# Nexie.net
KiCad netlist of a schematic drawn in Altium Designer
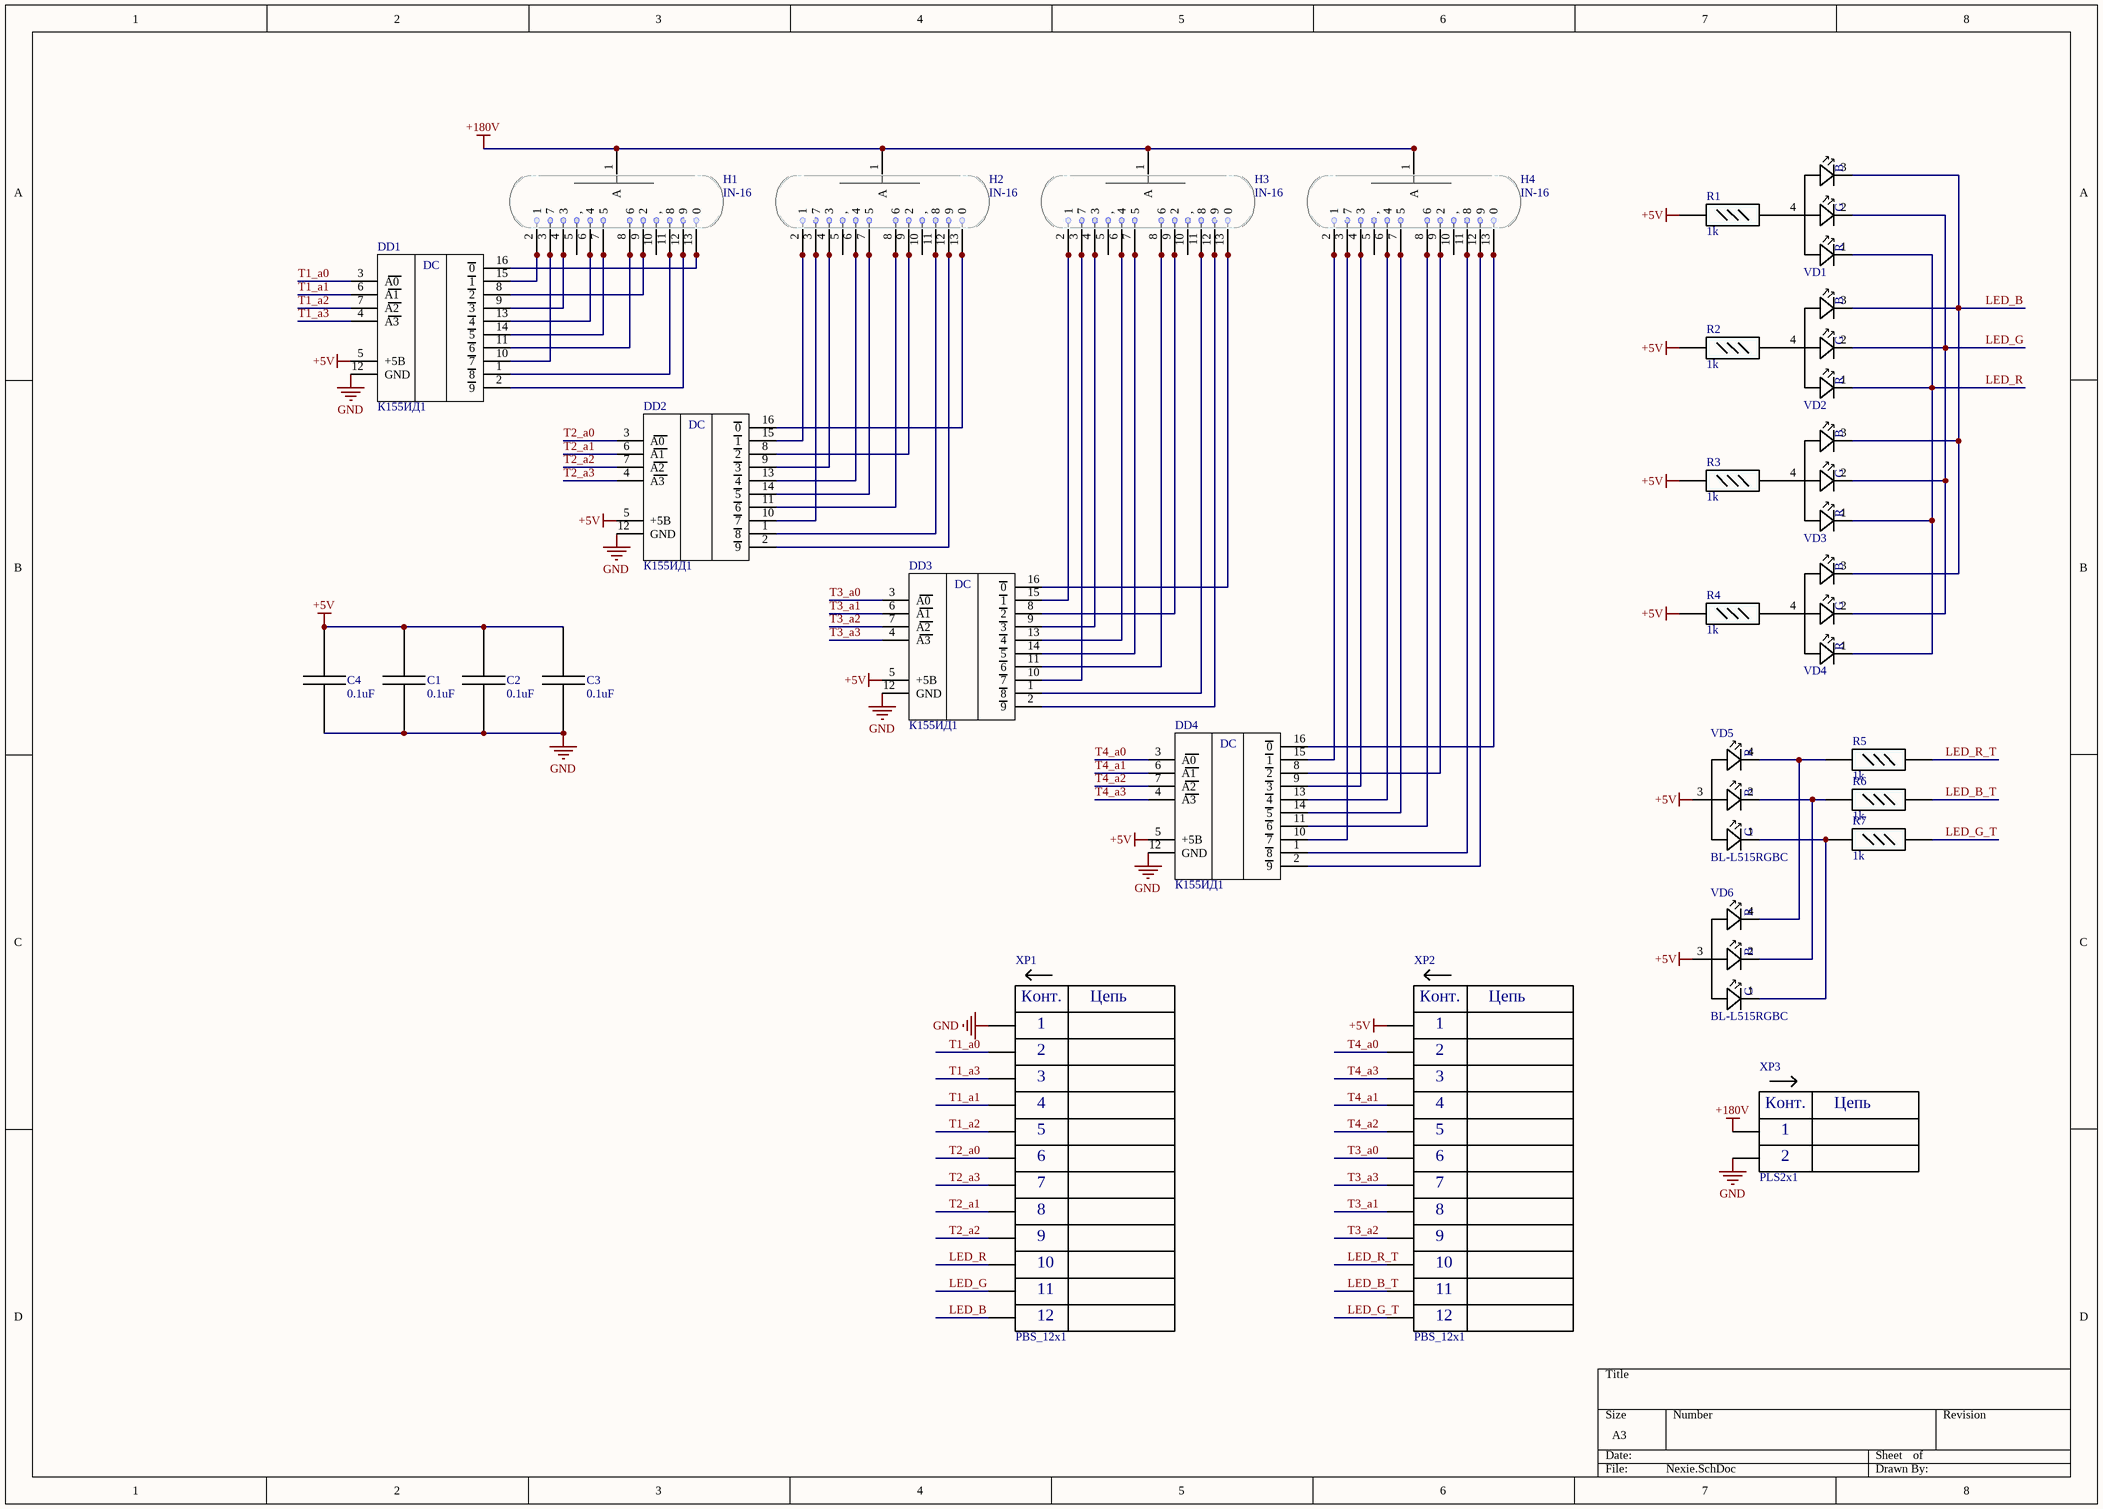
[diagram p0: Nexie.SchDoc]

(export (version "E")
  (design (tool "Eeschema 10.0.6"))
  (components
    (comp (ref "C1")
      (value "0.1uF")
      (footprint "CAP_1206")
      (fields (field (name "Comment") "Cap_0"))
      (libsource (lib "Capacitor") (part "Cap_0"))
    )
    (comp (ref "C2")
      (value "0.1uF")
      (footprint "CAP_1206")
      (fields (field (name "Comment") "Cap_0"))
      (libsource (lib "Capacitor") (part "Cap_0"))
    )
    (comp (ref "C3")
      (value "0.1uF")
      (footprint "CAP_1206")
      (fields (field (name "Comment") "Cap_0"))
      (libsource (lib "Capacitor") (part "Cap_0"))
    )
    (comp (ref "C4")
      (value "0.1uF")
      (footprint "CAP_1206")
      (fields (field (name "Comment") "Cap_0"))
      (libsource (lib "Capacitor") (part "Cap_0"))
    )
    (comp (ref "DD1") (value "К155ИД1") (footprint "К155ИД1") (libsource (lib "K155") (part "К155ИД1")))
    (comp (ref "DD2") (value "К155ИД1") (footprint "К155ИД1") (libsource (lib "K155") (part "К155ИД1")))
    (comp (ref "DD3") (value "К155ИД1") (footprint "К155ИД1") (libsource (lib "K155") (part "К155ИД1")))
    (comp (ref "DD4") (value "К155ИД1") (footprint "К155ИД1") (libsource (lib "K155") (part "К155ИД1")))
    (comp (ref "H1") (value "IN-16") (footprint "IN_16_tube") (libsource (lib "TUBE") (part "IN-16")))
    (comp (ref "H2") (value "IN-16") (footprint "IN_16_tube") (libsource (lib "TUBE") (part "IN-16")))
    (comp (ref "H3") (value "IN-16") (footprint "IN_16_tube") (libsource (lib "TUBE") (part "IN-16")))
    (comp (ref "H4") (value "IN-16") (footprint "IN_16_tube") (libsource (lib "TUBE") (part "IN-16")))
    (comp (ref "R1")
      (value "1k")
      (footprint "Resistor_0402")
      (fields (field (name "Comment") "Resistors_0.05W"))
      (libsource (lib "Resistors") (part "Resistors_0.05W"))
    )
    (comp (ref "R2")
      (value "1k")
      (footprint "Resistor_0402")
      (fields (field (name "Comment") "Resistors_0.05W"))
      (libsource (lib "Resistors") (part "Resistors_0.05W"))
    )
    (comp (ref "R3")
      (value "1k")
      (footprint "Resistor_0402")
      (fields (field (name "Comment") "Resistors_0.05W"))
      (libsource (lib "Resistors") (part "Resistors_0.05W"))
    )
    (comp (ref "R4")
      (value "1k")
      (footprint "Resistor_0402")
      (fields (field (name "Comment") "Resistors_0.05W"))
      (libsource (lib "Resistors") (part "Resistors_0.05W"))
    )
    (comp (ref "R5")
      (value "1k")
      (footprint "Resistor_0402")
      (fields (field (name "Comment") "Resistors_0.05W"))
      (libsource (lib "Resistors") (part "Resistors_0.05W"))
    )
    (comp (ref "R6")
      (value "1k")
      (footprint "Resistor_0402")
      (fields (field (name "Comment") "Resistors_0.05W"))
      (libsource (lib "Resistors") (part "Resistors_0.05W"))
    )
    (comp (ref "R7")
      (value "1k")
      (footprint "Resistor_0402")
      (fields (field (name "Comment") "Resistors_0.05W"))
      (libsource (lib "Resistors") (part "Resistors_0.05W"))
    )
    (comp (ref "VD1")
      (value "TO-3228BC-MRPBFGF")
      (footprint "TO-3228BC-MRPBFGF")
      (libsource (lib "LED") (part "TO-3228BC-MRPBFGF"))
    )
    (comp (ref "VD2")
      (value "TO-3228BC-MRPBFGF")
      (footprint "TO-3228BC-MRPBFGF")
      (libsource (lib "LED") (part "TO-3228BC-MRPBFGF"))
    )
    (comp (ref "VD3")
      (value "TO-3228BC-MRPBFGF")
      (footprint "TO-3228BC-MRPBFGF")
      (libsource (lib "LED") (part "TO-3228BC-MRPBFGF"))
    )
    (comp (ref "VD4")
      (value "TO-3228BC-MRPBFGF")
      (footprint "TO-3228BC-MRPBFGF")
      (libsource (lib "LED") (part "TO-3228BC-MRPBFGF"))
    )
    (comp (ref "VD5")
      (value "BL-L515RGBC")
      (footprint "BL-L515RGBC")
      (libsource (lib "LED") (part "BL-L515RGBC"))
    )
    (comp (ref "VD6")
      (value "BL-L515RGBC")
      (footprint "BL-L515RGBC")
      (libsource (lib "LED") (part "BL-L515RGBC"))
    )
    (comp (ref "XP1")
      (value "PBS_12x1")
      (footprint "PBS_12x1")
      (libsource (lib "Connectors") (part "PBS_12x1"))
    )
    (comp (ref "XP2")
      (value "PBS_12x1")
      (footprint "PBS_12x1")
      (libsource (lib "Connectors") (part "PBS_12x1"))
    )
    (comp (ref "XP3") (value "PLS2x1") (footprint "PLS2x1") (libsource (lib "Connectors") (part "PLS2x1")))
  )
  (nets
    (net (code "1") (name "+5V") (class "Default")
      (node (ref "C1") (pin "2") (pinfunction "2_2") (pintype "passive"))
      (node (ref "C2") (pin "2") (pinfunction "2_2") (pintype "passive"))
      (node (ref "C3") (pin "2") (pinfunction "2_2") (pintype "passive"))
      (node (ref "C4") (pin "2") (pinfunction "2_2") (pintype "passive"))
      (node (ref "DD1") (pin "5") (pinfunction "+5В_5") (pintype "passive"))
      (node (ref "DD2") (pin "5") (pinfunction "+5В_5") (pintype "passive"))
      (node (ref "DD3") (pin "5") (pinfunction "+5В_5") (pintype "passive"))
      (node (ref "DD4") (pin "5") (pinfunction "+5В_5") (pintype "passive"))
      (node (ref "R1") (pin "1") (pinfunction "1_1") (pintype "passive"))
      (node (ref "R2") (pin "1") (pinfunction "1_1") (pintype "passive"))
      (node (ref "R3") (pin "1") (pinfunction "1_1") (pintype "passive"))
      (node (ref "R4") (pin "1") (pinfunction "1_1") (pintype "passive"))
      (node (ref "VD5") (pin "3") (pintype "passive"))
      (node (ref "VD6") (pin "3") (pintype "passive"))
      (node (ref "XP2") (pin "1") (pinfunction "1_1") (pintype "passive"))
    )
    (net (code "2") (name "+180V") (class "Default")
      (node (ref "H1") (pin "1") (pinfunction "A_1") (pintype "passive"))
      (node (ref "H2") (pin "1") (pinfunction "A_1") (pintype "passive"))
      (node (ref "H3") (pin "1") (pinfunction "A_1") (pintype "passive"))
      (node (ref "H4") (pin "1") (pinfunction "A_1") (pintype "passive"))
      (node (ref "XP3") (pin "1") (pinfunction "1_1") (pintype "passive"))
    )
    (net (code "3") (name "/LED_B") (class "Default")
      (node (ref "VD1") (pin "3") (pinfunction "B_3") (pintype "passive"))
      (node (ref "VD2") (pin "3") (pinfunction "B_3") (pintype "passive"))
      (node (ref "VD3") (pin "3") (pinfunction "B_3") (pintype "passive"))
      (node (ref "VD4") (pin "3") (pinfunction "B_3") (pintype "passive"))
      (node (ref "XP1") (pin "12") (pinfunction "12_12") (pintype "passive"))
    )
    (net (code "4") (name "/LED_B_T") (class "Default")
      (node (ref "R6") (pin "2") (pinfunction "2_2") (pintype "passive"))
      (node (ref "XP2") (pin "11") (pinfunction "11_11") (pintype "passive"))
    )
    (net (code "5") (name "/LED_G") (class "Default")
      (node (ref "VD1") (pin "2") (pinfunction "G_2") (pintype "passive"))
      (node (ref "VD2") (pin "2") (pinfunction "G_2") (pintype "passive"))
      (node (ref "VD3") (pin "2") (pinfunction "G_2") (pintype "passive"))
      (node (ref "VD4") (pin "2") (pinfunction "G_2") (pintype "passive"))
      (node (ref "XP1") (pin "11") (pinfunction "11_11") (pintype "passive"))
    )
    (net (code "6") (name "/LED_G_T") (class "Default")
      (node (ref "R7") (pin "2") (pinfunction "2_2") (pintype "passive"))
      (node (ref "XP2") (pin "12") (pinfunction "12_12") (pintype "passive"))
    )
    (net (code "7") (name "/LED_R") (class "Default")
      (node (ref "VD1") (pin "1") (pinfunction "R_1") (pintype "passive"))
      (node (ref "VD2") (pin "1") (pinfunction "R_1") (pintype "passive"))
      (node (ref "VD3") (pin "1") (pinfunction "R_1") (pintype "passive"))
      (node (ref "VD4") (pin "1") (pinfunction "R_1") (pintype "passive"))
      (node (ref "XP1") (pin "10") (pinfunction "10_10") (pintype "passive"))
    )
    (net (code "8") (name "/LED_R_T") (class "Default")
      (node (ref "R5") (pin "2") (pinfunction "2_2") (pintype "passive"))
      (node (ref "XP2") (pin "10") (pinfunction "10_10") (pintype "passive"))
    )
    (net (code "9") (name "/T1_a0") (class "Default")
      (node (ref "DD1") (pin "3") (pinfunction "А0_3") (pintype "passive"))
      (node (ref "XP1") (pin "2") (pinfunction "2_2") (pintype "passive"))
    )
    (net (code "10") (name "/T1_a1") (class "Default")
      (node (ref "DD1") (pin "6") (pinfunction "А1_6") (pintype "passive"))
      (node (ref "XP1") (pin "4") (pinfunction "4_4") (pintype "passive"))
    )
    (net (code "11") (name "/T1_a2") (class "Default")
      (node (ref "DD1") (pin "7") (pinfunction "А2_7") (pintype "passive"))
      (node (ref "XP1") (pin "5") (pinfunction "5_5") (pintype "passive"))
    )
    (net (code "12") (name "/T1_a3") (class "Default")
      (node (ref "DD1") (pin "4") (pinfunction "А3_4") (pintype "passive"))
      (node (ref "XP1") (pin "3") (pinfunction "3_3") (pintype "passive"))
    )
    (net (code "13") (name "/T2_a0") (class "Default")
      (node (ref "DD2") (pin "3") (pinfunction "А0_3") (pintype "passive"))
      (node (ref "XP1") (pin "6") (pinfunction "6_6") (pintype "passive"))
    )
    (net (code "14") (name "/T2_a1") (class "Default")
      (node (ref "DD2") (pin "6") (pinfunction "А1_6") (pintype "passive"))
      (node (ref "XP1") (pin "8") (pinfunction "8_8") (pintype "passive"))
    )
    (net (code "15") (name "/T2_a2") (class "Default")
      (node (ref "DD2") (pin "7") (pinfunction "А2_7") (pintype "passive"))
      (node (ref "XP1") (pin "9") (pinfunction "9_9") (pintype "passive"))
    )
    (net (code "16") (name "/T2_a3") (class "Default")
      (node (ref "DD2") (pin "4") (pinfunction "А3_4") (pintype "passive"))
      (node (ref "XP1") (pin "7") (pinfunction "7_7") (pintype "passive"))
    )
    (net (code "17") (name "/T3_a0") (class "Default")
      (node (ref "DD3") (pin "3") (pinfunction "А0_3") (pintype "passive"))
      (node (ref "XP2") (pin "6") (pinfunction "6_6") (pintype "passive"))
    )
    (net (code "18") (name "/T3_a1") (class "Default")
      (node (ref "DD3") (pin "6") (pinfunction "А1_6") (pintype "passive"))
      (node (ref "XP2") (pin "8") (pinfunction "8_8") (pintype "passive"))
    )
    (net (code "19") (name "/T3_a2") (class "Default")
      (node (ref "DD3") (pin "7") (pinfunction "А2_7") (pintype "passive"))
      (node (ref "XP2") (pin "9") (pinfunction "9_9") (pintype "passive"))
    )
    (net (code "20") (name "/T3_a3") (class "Default")
      (node (ref "DD3") (pin "4") (pinfunction "А3_4") (pintype "passive"))
      (node (ref "XP2") (pin "7") (pinfunction "7_7") (pintype "passive"))
    )
    (net (code "21") (name "/T4_a0") (class "Default")
      (node (ref "DD4") (pin "3") (pinfunction "А0_3") (pintype "passive"))
      (node (ref "XP2") (pin "2") (pinfunction "2_2") (pintype "passive"))
    )
    (net (code "22") (name "/T4_a1") (class "Default")
      (node (ref "DD4") (pin "6") (pinfunction "А1_6") (pintype "passive"))
      (node (ref "XP2") (pin "4") (pinfunction "4_4") (pintype "passive"))
    )
    (net (code "23") (name "/T4_a2") (class "Default")
      (node (ref "DD4") (pin "7") (pinfunction "А2_7") (pintype "passive"))
      (node (ref "XP2") (pin "5") (pinfunction "5_5") (pintype "passive"))
    )
    (net (code "24") (name "/T4_a3") (class "Default")
      (node (ref "DD4") (pin "4") (pinfunction "А3_4") (pintype "passive"))
      (node (ref "XP2") (pin "3") (pinfunction "3_3") (pintype "passive"))
    )
    (net (code "25") (name "GND") (class "Default")
      (node (ref "C1") (pin "1") (pinfunction "1_1") (pintype "passive"))
      (node (ref "C2") (pin "1") (pinfunction "1_1") (pintype "passive"))
      (node (ref "C3") (pin "1") (pinfunction "1_1") (pintype "passive"))
      (node (ref "C4") (pin "1") (pinfunction "1_1") (pintype "passive"))
      (node (ref "DD1") (pin "12") (pinfunction "GND_12") (pintype "passive"))
      (node (ref "DD2") (pin "12") (pinfunction "GND_12") (pintype "passive"))
      (node (ref "DD3") (pin "12") (pinfunction "GND_12") (pintype "passive"))
      (node (ref "DD4") (pin "12") (pinfunction "GND_12") (pintype "passive"))
      (node (ref "XP1") (pin "1") (pinfunction "1_1") (pintype "passive"))
      (node (ref "XP3") (pin "2") (pinfunction "2_2") (pintype "passive"))
    )
    (net (code "26") (name "Net-(DD1-0)") (class "Default")
      (node (ref "DD1") (pin "16") (pinfunction "0_16") (pintype "passive"))
      (node (ref "H1") (pin "13") (pinfunction "0_13") (pintype "passive"))
    )
    (net (code "27") (name "Net-(DD1-1)") (class "Default")
      (node (ref "DD1") (pin "15") (pinfunction "1_15") (pintype "passive"))
      (node (ref "H1") (pin "2") (pinfunction "1_2") (pintype "passive"))
    )
    (net (code "28") (name "Net-(DD1-2)") (class "Default")
      (node (ref "DD1") (pin "8") (pinfunction "2_8") (pintype "passive"))
      (node (ref "H1") (pin "9") (pinfunction "2_9") (pintype "passive"))
    )
    (net (code "29") (name "Net-(DD1-3)") (class "Default")
      (node (ref "DD1") (pin "9") (pinfunction "3_9") (pintype "passive"))
      (node (ref "H1") (pin "4") (pinfunction "3_4") (pintype "passive"))
    )
    (net (code "30") (name "Net-(DD1-4)") (class "Default")
      (node (ref "DD1") (pin "13") (pinfunction "4_13") (pintype "passive"))
      (node (ref "H1") (pin "6") (pinfunction "4_6") (pintype "passive"))
    )
    (net (code "31") (name "Net-(DD1-5)") (class "Default")
      (node (ref "DD1") (pin "14") (pinfunction "5_14") (pintype "passive"))
      (node (ref "H1") (pin "7") (pinfunction "5_7") (pintype "passive"))
    )
    (net (code "32") (name "Net-(DD1-6)") (class "Default")
      (node (ref "DD1") (pin "11") (pinfunction "6_11") (pintype "passive"))
      (node (ref "H1") (pin "8") (pinfunction "6_8") (pintype "passive"))
    )
    (net (code "33") (name "Net-(DD1-7)") (class "Default")
      (node (ref "DD1") (pin "10") (pinfunction "7_10") (pintype "passive"))
      (node (ref "H1") (pin "3") (pinfunction "7_3") (pintype "passive"))
    )
    (net (code "34") (name "Net-(DD1-8)") (class "Default")
      (node (ref "DD1") (pin "1") (pinfunction "8_1") (pintype "passive"))
      (node (ref "H1") (pin "11") (pinfunction "8_11") (pintype "passive"))
    )
    (net (code "35") (name "Net-(DD1-9)") (class "Default")
      (node (ref "DD1") (pin "2") (pinfunction "9_2") (pintype "passive"))
      (node (ref "H1") (pin "12") (pinfunction "9_12") (pintype "passive"))
    )
    (net (code "36") (name "Net-(DD2-0)") (class "Default")
      (node (ref "DD2") (pin "16") (pinfunction "0_16") (pintype "passive"))
      (node (ref "H2") (pin "13") (pinfunction "0_13") (pintype "passive"))
    )
    (net (code "37") (name "Net-(DD2-1)") (class "Default")
      (node (ref "DD2") (pin "15") (pinfunction "1_15") (pintype "passive"))
      (node (ref "H2") (pin "2") (pinfunction "1_2") (pintype "passive"))
    )
    (net (code "38") (name "Net-(DD2-2)") (class "Default")
      (node (ref "DD2") (pin "8") (pinfunction "2_8") (pintype "passive"))
      (node (ref "H2") (pin "9") (pinfunction "2_9") (pintype "passive"))
    )
    (net (code "39") (name "Net-(DD2-3)") (class "Default")
      (node (ref "DD2") (pin "9") (pinfunction "3_9") (pintype "passive"))
      (node (ref "H2") (pin "4") (pinfunction "3_4") (pintype "passive"))
    )
    (net (code "40") (name "Net-(DD2-4)") (class "Default")
      (node (ref "DD2") (pin "13") (pinfunction "4_13") (pintype "passive"))
      (node (ref "H2") (pin "6") (pinfunction "4_6") (pintype "passive"))
    )
    (net (code "41") (name "Net-(DD2-5)") (class "Default")
      (node (ref "DD2") (pin "14") (pinfunction "5_14") (pintype "passive"))
      (node (ref "H2") (pin "7") (pinfunction "5_7") (pintype "passive"))
    )
    (net (code "42") (name "Net-(DD2-6)") (class "Default")
      (node (ref "DD2") (pin "11") (pinfunction "6_11") (pintype "passive"))
      (node (ref "H2") (pin "8") (pinfunction "6_8") (pintype "passive"))
    )
    (net (code "43") (name "Net-(DD2-7)") (class "Default")
      (node (ref "DD2") (pin "10") (pinfunction "7_10") (pintype "passive"))
      (node (ref "H2") (pin "3") (pinfunction "7_3") (pintype "passive"))
    )
    (net (code "44") (name "Net-(DD2-8)") (class "Default")
      (node (ref "DD2") (pin "1") (pinfunction "8_1") (pintype "passive"))
      (node (ref "H2") (pin "11") (pinfunction "8_11") (pintype "passive"))
    )
    (net (code "45") (name "Net-(DD2-9)") (class "Default")
      (node (ref "DD2") (pin "2") (pinfunction "9_2") (pintype "passive"))
      (node (ref "H2") (pin "12") (pinfunction "9_12") (pintype "passive"))
    )
    (net (code "46") (name "Net-(DD3-0)") (class "Default")
      (node (ref "DD3") (pin "16") (pinfunction "0_16") (pintype "passive"))
      (node (ref "H3") (pin "13") (pinfunction "0_13") (pintype "passive"))
    )
    (net (code "47") (name "Net-(DD3-1)") (class "Default")
      (node (ref "DD3") (pin "15") (pinfunction "1_15") (pintype "passive"))
      (node (ref "H3") (pin "2") (pinfunction "1_2") (pintype "passive"))
    )
    (net (code "48") (name "Net-(DD3-2)") (class "Default")
      (node (ref "DD3") (pin "8") (pinfunction "2_8") (pintype "passive"))
      (node (ref "H3") (pin "9") (pinfunction "2_9") (pintype "passive"))
    )
    (net (code "49") (name "Net-(DD3-3)") (class "Default")
      (node (ref "DD3") (pin "9") (pinfunction "3_9") (pintype "passive"))
      (node (ref "H3") (pin "4") (pinfunction "3_4") (pintype "passive"))
    )
    (net (code "50") (name "Net-(DD3-4)") (class "Default")
      (node (ref "DD3") (pin "13") (pinfunction "4_13") (pintype "passive"))
      (node (ref "H3") (pin "6") (pinfunction "4_6") (pintype "passive"))
    )
    (net (code "51") (name "Net-(DD3-5)") (class "Default")
      (node (ref "DD3") (pin "14") (pinfunction "5_14") (pintype "passive"))
      (node (ref "H3") (pin "7") (pinfunction "5_7") (pintype "passive"))
    )
    (net (code "52") (name "Net-(DD3-6)") (class "Default")
      (node (ref "DD3") (pin "11") (pinfunction "6_11") (pintype "passive"))
      (node (ref "H3") (pin "8") (pinfunction "6_8") (pintype "passive"))
    )
    (net (code "53") (name "Net-(DD3-7)") (class "Default")
      (node (ref "DD3") (pin "10") (pinfunction "7_10") (pintype "passive"))
      (node (ref "H3") (pin "3") (pinfunction "7_3") (pintype "passive"))
    )
    (net (code "54") (name "Net-(DD3-8)") (class "Default")
      (node (ref "DD3") (pin "1") (pinfunction "8_1") (pintype "passive"))
      (node (ref "H3") (pin "11") (pinfunction "8_11") (pintype "passive"))
    )
    (net (code "55") (name "Net-(DD3-9)") (class "Default")
      (node (ref "DD3") (pin "2") (pinfunction "9_2") (pintype "passive"))
      (node (ref "H3") (pin "12") (pinfunction "9_12") (pintype "passive"))
    )
    (net (code "56") (name "Net-(DD4-0)") (class "Default")
      (node (ref "DD4") (pin "16") (pinfunction "0_16") (pintype "passive"))
      (node (ref "H4") (pin "13") (pinfunction "0_13") (pintype "passive"))
    )
    (net (code "57") (name "Net-(DD4-1)") (class "Default")
      (node (ref "DD4") (pin "15") (pinfunction "1_15") (pintype "passive"))
      (node (ref "H4") (pin "2") (pinfunction "1_2") (pintype "passive"))
    )
    (net (code "58") (name "Net-(DD4-2)") (class "Default")
      (node (ref "DD4") (pin "8") (pinfunction "2_8") (pintype "passive"))
      (node (ref "H4") (pin "9") (pinfunction "2_9") (pintype "passive"))
    )
    (net (code "59") (name "Net-(DD4-3)") (class "Default")
      (node (ref "DD4") (pin "9") (pinfunction "3_9") (pintype "passive"))
      (node (ref "H4") (pin "4") (pinfunction "3_4") (pintype "passive"))
    )
    (net (code "60") (name "Net-(DD4-4)") (class "Default")
      (node (ref "DD4") (pin "13") (pinfunction "4_13") (pintype "passive"))
      (node (ref "H4") (pin "6") (pinfunction "4_6") (pintype "passive"))
    )
    (net (code "61") (name "Net-(DD4-5)") (class "Default")
      (node (ref "DD4") (pin "14") (pinfunction "5_14") (pintype "passive"))
      (node (ref "H4") (pin "7") (pinfunction "5_7") (pintype "passive"))
    )
    (net (code "62") (name "Net-(DD4-6)") (class "Default")
      (node (ref "DD4") (pin "11") (pinfunction "6_11") (pintype "passive"))
      (node (ref "H4") (pin "8") (pinfunction "6_8") (pintype "passive"))
    )
    (net (code "63") (name "Net-(DD4-7)") (class "Default")
      (node (ref "DD4") (pin "10") (pinfunction "7_10") (pintype "passive"))
      (node (ref "H4") (pin "3") (pinfunction "7_3") (pintype "passive"))
    )
    (net (code "64") (name "Net-(DD4-8)") (class "Default")
      (node (ref "DD4") (pin "1") (pinfunction "8_1") (pintype "passive"))
      (node (ref "H4") (pin "11") (pinfunction "8_11") (pintype "passive"))
    )
    (net (code "65") (name "Net-(DD4-9)") (class "Default")
      (node (ref "DD4") (pin "2") (pinfunction "9_2") (pintype "passive"))
      (node (ref "H4") (pin "12") (pinfunction "9_12") (pintype "passive"))
    )
    (net (code "66") (name "Net-(R1-Pad2)") (class "Default")
      (node (ref "R1") (pin "2") (pinfunction "2_2") (pintype "passive"))
      (node (ref "VD1") (pin "4") (pintype "passive"))
    )
    (net (code "67") (name "Net-(R2-Pad2)") (class "Default")
      (node (ref "R2") (pin "2") (pinfunction "2_2") (pintype "passive"))
      (node (ref "VD2") (pin "4") (pintype "passive"))
    )
    (net (code "68") (name "Net-(R3-Pad2)") (class "Default")
      (node (ref "R3") (pin "2") (pinfunction "2_2") (pintype "passive"))
      (node (ref "VD3") (pin "4") (pintype "passive"))
    )
    (net (code "69") (name "Net-(R4-Pad2)") (class "Default")
      (node (ref "R4") (pin "2") (pinfunction "2_2") (pintype "passive"))
      (node (ref "VD4") (pin "4") (pintype "passive"))
    )
    (net (code "70") (name "Net-(VD5-B)") (class "Default")
      (node (ref "R5") (pin "1") (pinfunction "1_1") (pintype "passive"))
      (node (ref "VD5") (pin "4") (pinfunction "B_4") (pintype "passive"))
      (node (ref "VD6") (pin "4") (pinfunction "B_4") (pintype "passive"))
    )
    (net (code "71") (name "Net-(VD5-G)") (class "Default")
      (node (ref "R6") (pin "1") (pinfunction "1_1") (pintype "passive"))
      (node (ref "VD5") (pin "2") (pinfunction "G_2") (pintype "passive"))
      (node (ref "VD6") (pin "2") (pinfunction "G_2") (pintype "passive"))
    )
    (net (code "72") (name "Net-(VD5-R)") (class "Default")
      (node (ref "R7") (pin "1") (pinfunction "1_1") (pintype "passive"))
      (node (ref "VD5") (pin "1") (pinfunction "R_1") (pintype "passive"))
      (node (ref "VD6") (pin "1") (pinfunction "R_1") (pintype "passive"))
    )
    (net (code "73") (name "unconnected-(H1-,-Pad5)") (class "Default")
      (node (ref "H1") (pin "5") (pinfunction ",_5") (pintype "passive"))
    )
    (net (code "74") (name "unconnected-(H1-,-Pad10)") (class "Default")
      (node (ref "H1") (pin "10") (pinfunction ",_10") (pintype "passive"))
    )
    (net (code "75") (name "unconnected-(H2-,-Pad5)") (class "Default")
      (node (ref "H2") (pin "5") (pinfunction ",_5") (pintype "passive"))
    )
    (net (code "76") (name "unconnected-(H2-,-Pad10)") (class "Default")
      (node (ref "H2") (pin "10") (pinfunction ",_10") (pintype "passive"))
    )
    (net (code "77") (name "unconnected-(H3-,-Pad5)") (class "Default")
      (node (ref "H3") (pin "5") (pinfunction ",_5") (pintype "passive"))
    )
    (net (code "78") (name "unconnected-(H3-,-Pad10)") (class "Default")
      (node (ref "H3") (pin "10") (pinfunction ",_10") (pintype "passive"))
    )
    (net (code "79") (name "unconnected-(H4-,-Pad5)") (class "Default")
      (node (ref "H4") (pin "5") (pinfunction ",_5") (pintype "passive"))
    )
    (net (code "80") (name "unconnected-(H4-,-Pad10)") (class "Default")
      (node (ref "H4") (pin "10") (pinfunction ",_10") (pintype "passive"))
    )
  )
)
